# VotronicSRDuoDig_connector.net
KiCad netlist of a schematic drawn in EAGLE
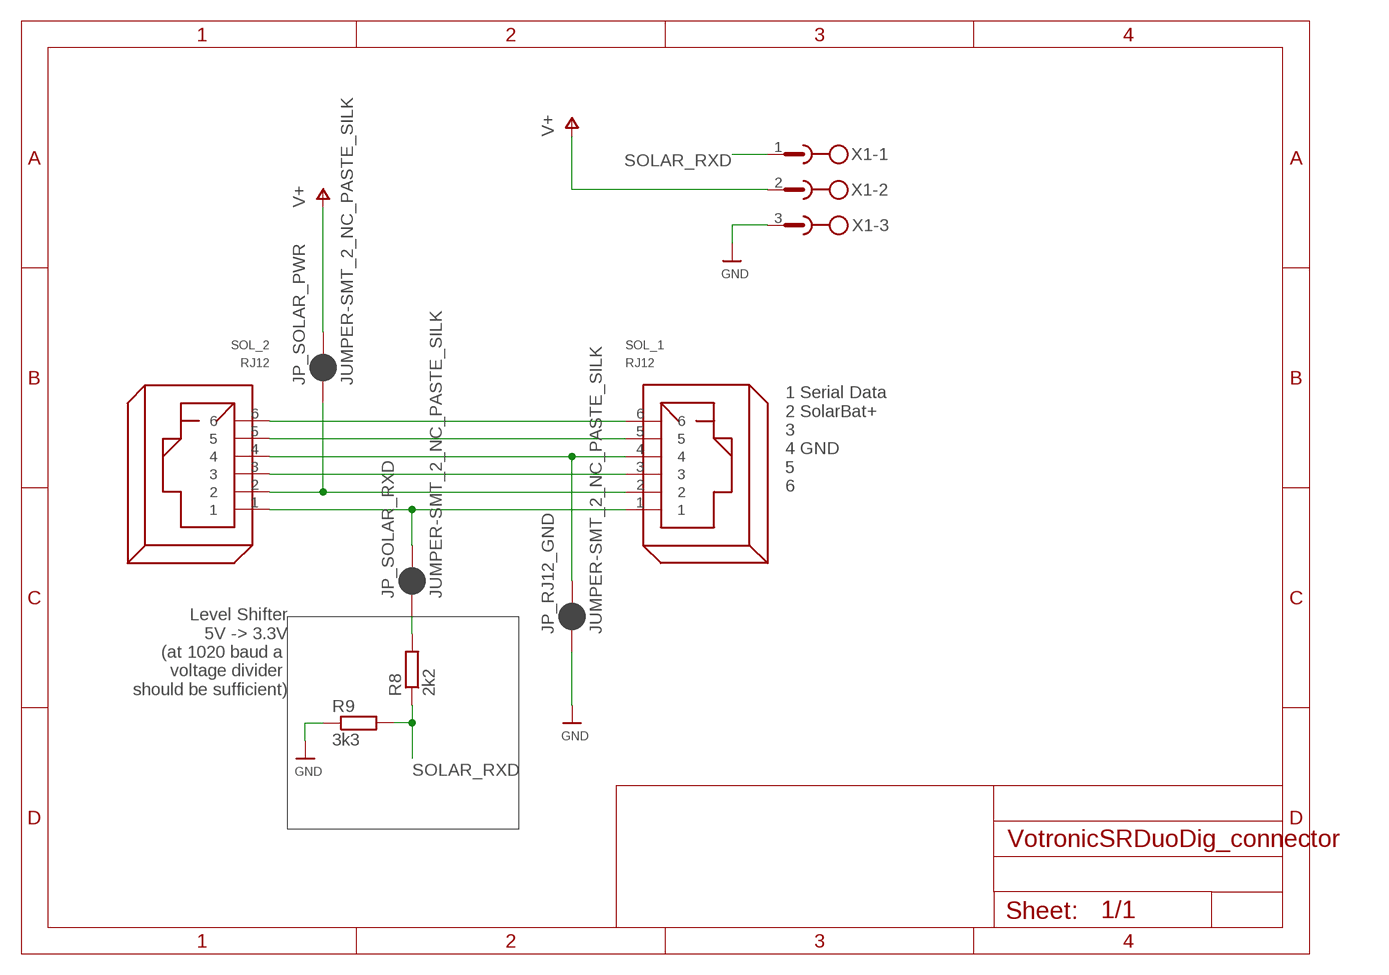
[diagram p0: schematic, sheet 1]

(export (version "E")
  (design (tool "Eeschema 10.0.6"))
  (components
    (comp (ref "JP_RJ12_GND")
      (value "JUMPER-SMT_2_NC_PASTE_SILK")
      (footprint "eagle-import:SMT-JUMPER_2_NC_PASTE_SILK")
      (libsource (lib "eagle-import") (part "JUMPER-SMT_2_NC_PASTE_SILK"))
    )
    (comp (ref "JP_SOLAR_PWR")
      (value "JUMPER-SMT_2_NC_PASTE_SILK")
      (footprint "eagle-import:SMT-JUMPER_2_NC_PASTE_SILK")
      (libsource (lib "eagle-import") (part "JUMPER-SMT_2_NC_PASTE_SILK"))
    )
    (comp (ref "JP_SOLAR_RXD")
      (value "JUMPER-SMT_2_NC_PASTE_SILK")
      (footprint "eagle-import:SMT-JUMPER_2_NC_PASTE_SILK")
      (libsource (lib "eagle-import") (part "JUMPER-SMT_2_NC_PASTE_SILK"))
    )
    (comp (ref "R8")
      (value "2k2")
      (footprint "eagle-import:R0805")
      (libsource (lib "eagle-import") (part "R-EU_R0805"))
    )
    (comp (ref "R9")
      (value "3k3")
      (footprint "eagle-import:R0805")
      (libsource (lib "eagle-import") (part "R-EU_R0805"))
    )
    (comp (ref "SOL_1")
      (value "RJ12")
      (footprint "eagle-import:RJ12")
      (libsource (lib "eagle-import") (part "RJ12"))
    )
    (comp (ref "SOL_2")
      (value "RJ12")
      (footprint "eagle-import:RJ12")
      (libsource (lib "eagle-import") (part "RJ12"))
    )
    (comp (ref "X1")
      (value "W232-3")
      (footprint "eagle-import:W232-3")
      (libsource (lib "eagle-import") (part "W232-3"))
    )
  )
  (nets
    (net (code "1") (name "/SOLAR_RXD") (class "Default")
      (node (ref "R8") (pin "1") (pinfunction "1_1") (pintype "passive"))
      (node (ref "R9") (pin "2") (pinfunction "2_2") (pintype "passive"))
      (node (ref "X1") (pin "1") (pinfunction "SK_1") (pintype "passive"))
    )
    (net (code "2") (name "GND") (class "Default")
      (node (ref "JP_RJ12_GND") (pin "1") (pinfunction "1_1") (pintype "passive"))
      (node (ref "R9") (pin "1") (pinfunction "1_1") (pintype "passive"))
      (node (ref "X1") (pin "3") (pinfunction "SK_3") (pintype "passive"))
    )
    (net (code "3") (name "Net-(JP_RJ12_GND-Pad2)") (class "Default")
      (node (ref "JP_RJ12_GND") (pin "2") (pinfunction "2_2") (pintype "passive"))
      (node (ref "SOL_1") (pin "4") (pinfunction "4_4") (pintype "bidirectional"))
      (node (ref "SOL_2") (pin "4") (pinfunction "4_4") (pintype "bidirectional"))
    )
    (net (code "4") (name "Net-(JP_SOLAR_PWR-Pad1)") (class "Default")
      (node (ref "JP_SOLAR_PWR") (pin "1") (pinfunction "1_1") (pintype "passive"))
      (node (ref "SOL_1") (pin "2") (pinfunction "2_2") (pintype "bidirectional"))
      (node (ref "SOL_2") (pin "2") (pinfunction "2_2") (pintype "bidirectional"))
    )
    (net (code "5") (name "Net-(JP_SOLAR_RXD-Pad1)") (class "Default")
      (node (ref "JP_SOLAR_RXD") (pin "1") (pinfunction "1_1") (pintype "passive"))
      (node (ref "R8") (pin "2") (pinfunction "2_2") (pintype "passive"))
    )
    (net (code "6") (name "Net-(JP_SOLAR_RXD-Pad2)") (class "Default")
      (node (ref "JP_SOLAR_RXD") (pin "2") (pinfunction "2_2") (pintype "passive"))
      (node (ref "SOL_1") (pin "1") (pinfunction "1_1") (pintype "bidirectional"))
      (node (ref "SOL_2") (pin "1") (pinfunction "1_1") (pintype "bidirectional"))
    )
    (net (code "7") (name "Net-(SOL_1-Pad3)") (class "Default")
      (node (ref "SOL_1") (pin "3") (pinfunction "3_3") (pintype "bidirectional"))
      (node (ref "SOL_2") (pin "3") (pinfunction "3_3") (pintype "bidirectional"))
    )
    (net (code "8") (name "Net-(SOL_1-Pad5)") (class "Default")
      (node (ref "SOL_1") (pin "5") (pinfunction "5_5") (pintype "bidirectional"))
      (node (ref "SOL_2") (pin "5") (pinfunction "5_5") (pintype "bidirectional"))
    )
    (net (code "9") (name "Net-(SOL_1-Pad6)") (class "Default")
      (node (ref "SOL_1") (pin "6") (pinfunction "6_6") (pintype "bidirectional"))
      (node (ref "SOL_2") (pin "6") (pinfunction "6_6") (pintype "bidirectional"))
    )
    (net (code "10") (name "V+") (class "Default")
      (node (ref "JP_SOLAR_PWR") (pin "2") (pinfunction "2_2") (pintype "passive"))
      (node (ref "X1") (pin "2") (pinfunction "SK_2") (pintype "passive"))
    )
  )
)
